# tx_new.net
KiCad netlist of a schematic drawn in EAGLE
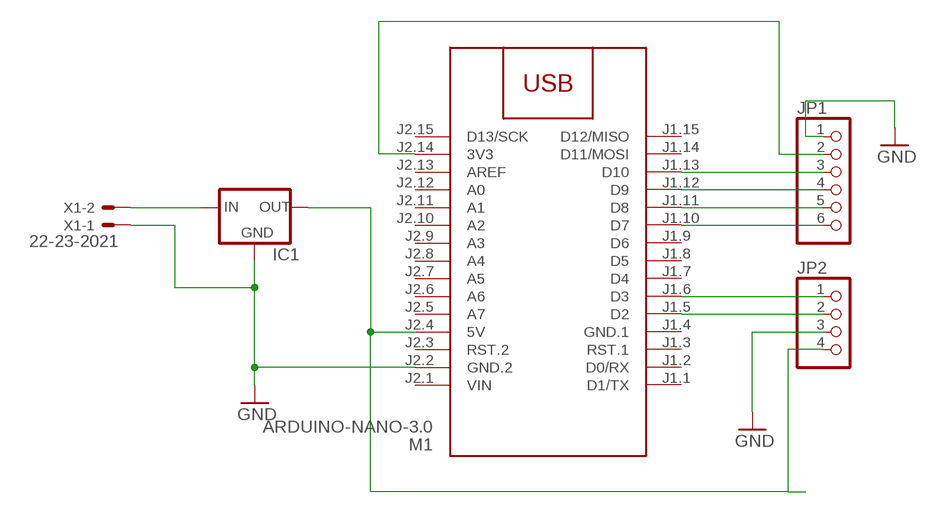
[diagram p0: schematic, sheet 1]

(export (version "E")
  (design (tool "Eeschema 10.0.6"))
  (components
    (comp (ref "IC1")
      (value "78XXS")
      (footprint "eagle-import:78XXS")
      (libsource (lib "eagle-import") (part "78XXS"))
    )
    (comp (ref "JP1")
      (value "PINHD-1X6")
      (footprint "eagle-import:1X06")
      (libsource (lib "eagle-import") (part "PINHD-1X6"))
    )
    (comp (ref "JP2")
      (value "PINHD-1X4")
      (footprint "eagle-import:1X04")
      (libsource (lib "eagle-import") (part "PINHD-1X4"))
    )
    (comp (ref "M1")
      (value "ARDUINO-NANO-3.0")
      (footprint "eagle-import:ARDUINO-NANO-3.0")
      (libsource (lib "eagle-import") (part "ARDUINO-NANO-3.0"))
    )
    (comp (ref "X1")
      (value "22-23-2021")
      (footprint "eagle-import:22-23-2021")
      (fields (field (name "MF") "MOLEX"))
      (libsource (lib "eagle-import") (part "22-23-2021"))
    )
  )
  (nets
    (net (code "1") (name "/GND.1") (class "Default")
      (node (ref "M1") (pin "J1.4") (pinfunction "GND.1_J1.4") (pintype "power_in"))
    )
    (net (code "2") (name "/VIN") (class "Default")
      (node (ref "M1") (pin "J2.1") (pinfunction "VIN_J2.1") (pintype "power_in"))
    )
    (net (code "3") (name "GND") (class "Default")
      (node (ref "IC1") (pin "GND") (pinfunction "GND_GND") (pintype "input"))
      (node (ref "JP1") (pin "1") (pinfunction "1_1") (pintype "passive"))
      (node (ref "JP2") (pin "3") (pinfunction "3_3") (pintype "passive"))
      (node (ref "M1") (pin "J2.2") (pinfunction "GND.2_J2.2") (pintype "power_in"))
      (node (ref "X1") (pin "1") (pinfunction "S_1") (pintype "passive"))
    )
    (net (code "4") (name "Net-(M1-3V3)") (class "Default")
      (node (ref "JP1") (pin "2") (pinfunction "2_2") (pintype "passive"))
      (node (ref "M1") (pin "J2.14") (pinfunction "3V3_J2.14") (pintype "power_in"))
    )
    (net (code "5") (name "Net-(M1-5V)") (class "Default")
      (node (ref "IC1") (pin "OUT") (pinfunction "OUT_OUT") (pintype "passive"))
      (node (ref "JP2") (pin "4") (pinfunction "4_4") (pintype "passive"))
      (node (ref "M1") (pin "J2.4") (pinfunction "5V_J2.4") (pintype "power_in"))
    )
    (net (code "6") (name "Net-(M1-D2)") (class "Default")
      (node (ref "JP2") (pin "2") (pinfunction "2_2") (pintype "passive"))
      (node (ref "M1") (pin "J1.5") (pinfunction "D2_J1.5") (pintype "bidirectional"))
    )
    (net (code "7") (name "Net-(M1-D3)") (class "Default")
      (node (ref "JP2") (pin "1") (pinfunction "1_1") (pintype "passive"))
      (node (ref "M1") (pin "J1.6") (pinfunction "D3_J1.6") (pintype "bidirectional"))
    )
    (net (code "8") (name "Net-(M1-D7)") (class "Default")
      (node (ref "JP1") (pin "6") (pinfunction "6_6") (pintype "passive"))
      (node (ref "M1") (pin "J1.10") (pinfunction "D7_J1.10") (pintype "bidirectional"))
    )
    (net (code "9") (name "Net-(M1-D8)") (class "Default")
      (node (ref "JP1") (pin "5") (pinfunction "5_5") (pintype "passive"))
      (node (ref "M1") (pin "J1.11") (pinfunction "D8_J1.11") (pintype "bidirectional"))
    )
    (net (code "10") (name "Net-(M1-D9)") (class "Default")
      (node (ref "JP1") (pin "4") (pinfunction "4_4") (pintype "passive"))
      (node (ref "M1") (pin "J1.12") (pinfunction "D9_J1.12") (pintype "bidirectional"))
    )
    (net (code "11") (name "Net-(M1-D10)") (class "Default")
      (node (ref "JP1") (pin "3") (pinfunction "3_3") (pintype "passive"))
      (node (ref "M1") (pin "J1.13") (pinfunction "D10_J1.13") (pintype "bidirectional"))
    )
    (net (code "12") (name "Net-(X1B-S)") (class "Default")
      (node (ref "IC1") (pin "IN") (pinfunction "IN_IN") (pintype "input"))
      (node (ref "X1") (pin "2") (pinfunction "S_2") (pintype "passive"))
    )
    (net (code "13") (name "unconnected-(M1-A0-PadJ2.12)") (class "Default")
      (node (ref "M1") (pin "J2.12") (pinfunction "A0_J2.12") (pintype "bidirectional"))
    )
    (net (code "14") (name "unconnected-(M1-A1-PadJ2.11)") (class "Default")
      (node (ref "M1") (pin "J2.11") (pinfunction "A1_J2.11") (pintype "bidirectional"))
    )
    (net (code "15") (name "unconnected-(M1-A2-PadJ2.10)") (class "Default")
      (node (ref "M1") (pin "J2.10") (pinfunction "A2_J2.10") (pintype "bidirectional"))
    )
    (net (code "16") (name "unconnected-(M1-A3-PadJ2.9)") (class "Default")
      (node (ref "M1") (pin "J2.9") (pinfunction "A3_J2.9") (pintype "bidirectional"))
    )
    (net (code "17") (name "unconnected-(M1-A4-PadJ2.8)") (class "Default")
      (node (ref "M1") (pin "J2.8") (pinfunction "A4_J2.8") (pintype "bidirectional"))
    )
    (net (code "18") (name "unconnected-(M1-A5-PadJ2.7)") (class "Default")
      (node (ref "M1") (pin "J2.7") (pinfunction "A5_J2.7") (pintype "bidirectional"))
    )
    (net (code "19") (name "unconnected-(M1-A6-PadJ2.6)") (class "Default")
      (node (ref "M1") (pin "J2.6") (pinfunction "A6_J2.6") (pintype "bidirectional"))
    )
    (net (code "20") (name "unconnected-(M1-A7-PadJ2.5)") (class "Default")
      (node (ref "M1") (pin "J2.5") (pinfunction "A7_J2.5") (pintype "bidirectional"))
    )
    (net (code "21") (name "unconnected-(M1-AREF-PadJ2.13)") (class "Default")
      (node (ref "M1") (pin "J2.13") (pinfunction "AREF_J2.13") (pintype "bidirectional"))
    )
    (net (code "22") (name "unconnected-(M1-D0{slash}RX-PadJ1.2)") (class "Default")
      (node (ref "M1") (pin "J1.2") (pinfunction "D0/RX_J1.2") (pintype "bidirectional"))
    )
    (net (code "23") (name "unconnected-(M1-D1{slash}TX-PadJ1.1)") (class "Default")
      (node (ref "M1") (pin "J1.1") (pinfunction "D1/TX_J1.1") (pintype "bidirectional"))
    )
    (net (code "24") (name "unconnected-(M1-D4-PadJ1.7)") (class "Default")
      (node (ref "M1") (pin "J1.7") (pinfunction "D4_J1.7") (pintype "bidirectional"))
    )
    (net (code "25") (name "unconnected-(M1-D5-PadJ1.8)") (class "Default")
      (node (ref "M1") (pin "J1.8") (pinfunction "D5_J1.8") (pintype "bidirectional"))
    )
    (net (code "26") (name "unconnected-(M1-D6-PadJ1.9)") (class "Default")
      (node (ref "M1") (pin "J1.9") (pinfunction "D6_J1.9") (pintype "bidirectional"))
    )
    (net (code "27") (name "unconnected-(M1-D11{slash}MOSI-PadJ1.14)") (class "Default")
      (node (ref "M1") (pin "J1.14") (pinfunction "D11/MOSI_J1.14") (pintype "bidirectional"))
    )
    (net (code "28") (name "unconnected-(M1-D12{slash}MISO-PadJ1.15)") (class "Default")
      (node (ref "M1") (pin "J1.15") (pinfunction "D12/MISO_J1.15") (pintype "bidirectional"))
    )
    (net (code "29") (name "unconnected-(M1-D13{slash}SCK-PadJ2.15)") (class "Default")
      (node (ref "M1") (pin "J2.15") (pinfunction "D13/SCK_J2.15") (pintype "bidirectional"))
    )
    (net (code "30") (name "unconnected-(M1-RST.1-PadJ1.3)") (class "Default")
      (node (ref "M1") (pin "J1.3") (pinfunction "RST.1_J1.3") (pintype "bidirectional"))
    )
    (net (code "31") (name "unconnected-(M1-RST.2-PadJ2.3)") (class "Default")
      (node (ref "M1") (pin "J2.3") (pinfunction "RST.2_J2.3") (pintype "bidirectional"))
    )
  )
)
